# main.net
KiCad netlist of a schematic drawn in Altium Designer
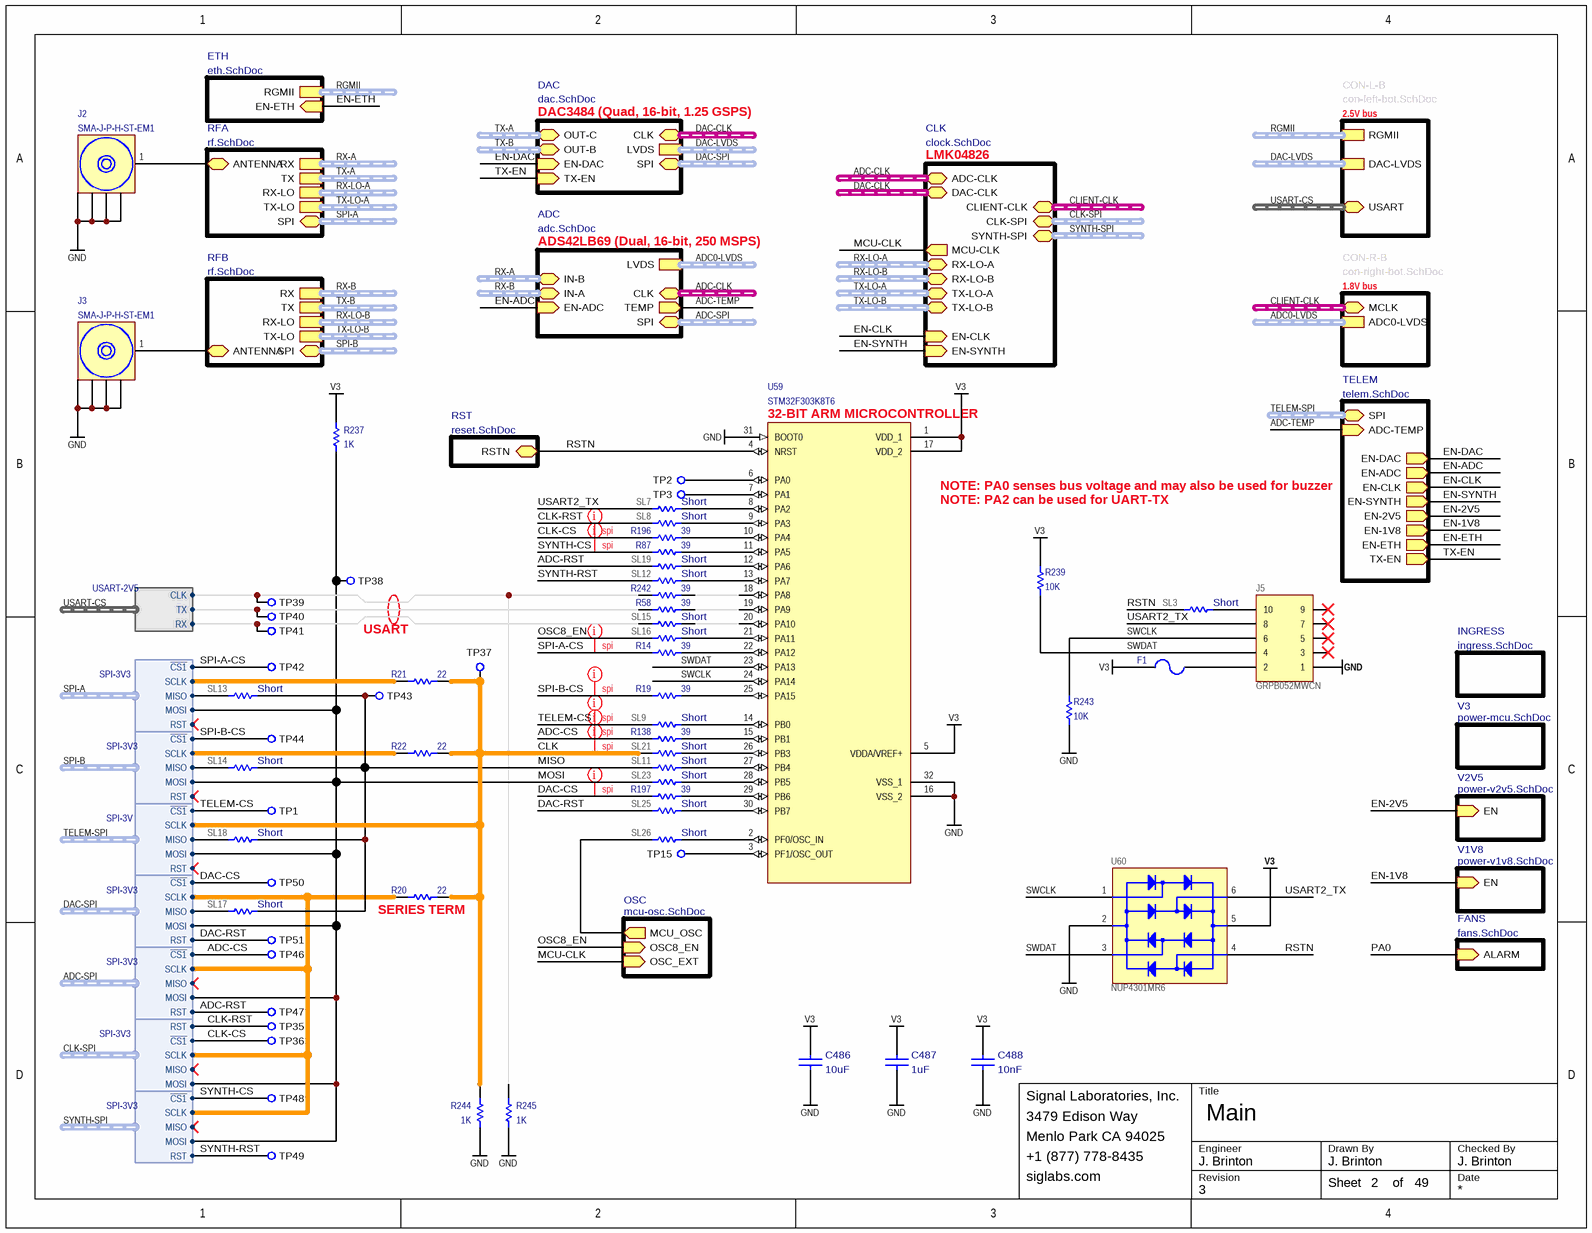
[diagram p0: main.SchDoc]

(export (version "E")
  (design (tool "Eeschema 10.0.6"))
  (components
    (comp (ref "C486")
      (value "10uF")
      (footprint "CAPC200X125X145L45N")
      (description "Ceramic Capacitor 10uF ±10% 16V X7R 0805")
      (fields (field (name "MANUFACTURER") "Samsung") (field (name "TOLERANCE") "±10%"))
      (libsource (lib "capacitors") (part "CAP"))
    )
    (comp (ref "C487")
      (value "1uF")
      (footprint "CAPC200X125X145L45N")
      (description "Ceramic Capacitor 1uF ±10% 25V X7R 0805")
      (fields (field (name "MANUFACTURER") "Taiyo Yuden") (field (name "TOLERANCE") "±10%"))
      (libsource (lib "capacitors") (part "CAP"))
    )
    (comp (ref "C488")
      (value "10nF")
      (footprint "CAPC100X50X55L25N")
      (description "Ceramic Capacitor 10nF ±10% 50V X7R 0402")
      (fields (field (name "MANUFACTURER") "Murata") (field (name "TOLERANCE") "±10%"))
      (libsource (lib "capacitors") (part "CAP"))
    )
    (comp (ref "F1")
      (value "0ZCJ0020FF2E")
      (footprint "generic:1206")
      (description "PTC Resettable Fuse, 0.2A, 30V, SMD 1206")
      (fields (field (name "MANUFACTURER") "Bell Fuse"))
      (libsource (lib "bel-fuse") (part "0ZCJ0020FF2E"))
    )
    (comp (ref "J2")
      (value "SMA-J-P-H-ST-EM1")
      (footprint "samtec:SMA-J-P-H-ST-EM1")
      (description "Edge Mount SMA Jack, Female Socket")
      (fields (field (name "MANUFACTURER") "Samtec"))
      (libsource (lib "amphenol") (part "132136"))
    )
    (comp (ref "J3")
      (value "SMA-J-P-H-ST-EM1")
      (footprint "samtec:SMA-J-P-H-ST-EM1")
      (description "Edge Mount SMA Jack, Female Socket")
      (fields (field (name "MANUFACTURER") "Samtec"))
      (libsource (lib "amphenol") (part "132136"))
    )
    (comp (ref "J5")
      (value "GRPB052MWCN")
      (footprint "sullins:GRPB052MWCN")
      (description "Male Header, 0.050\" Pitch, 2x5 Position, Right Angle")
      (fields (field (name "MANUFACTURER") "Sullins"))
      (libsource (lib "sullins") (part "GRPB052VWVN"))
    )
    (comp (ref "R14")
      (value "39")
      (footprint "RESC1005X40N")
      (description "Thick Film Resistor 39 ±1% 0402")
      (fields (field (name "MANUFACTURER") "Yageo") (field (name "TOLERANCE") "±1%"))
      (libsource (lib "Graviton") (part "RES 0402"))
    )
    (comp (ref "R19")
      (value "39")
      (footprint "RESC1005X40N")
      (description "Thick Film Resistor 39 ±1% 0402")
      (fields (field (name "MANUFACTURER") "Yageo") (field (name "TOLERANCE") "±1%"))
      (libsource (lib "Graviton") (part "RES 0402"))
    )
    (comp (ref "R20")
      (value "22")
      (footprint "RESC1005X40N")
      (description "Thick Film Resistor 22 ±1% 0402")
      (fields (field (name "MANUFACTURER") "Yageo") (field (name "TOLERANCE") "±1%"))
      (libsource (lib "Graviton") (part "RES 0402"))
    )
    (comp (ref "R21")
      (value "22")
      (footprint "RESC1005X40N")
      (description "Thick Film Resistor 22 ±1% 0402")
      (fields (field (name "MANUFACTURER") "Yageo") (field (name "TOLERANCE") "±1%"))
      (libsource (lib "Graviton") (part "RES 0402"))
    )
    (comp (ref "R22")
      (value "22")
      (footprint "RESC1005X40N")
      (description "Thick Film Resistor 22 ±1% 0402")
      (fields (field (name "MANUFACTURER") "Yageo") (field (name "TOLERANCE") "±1%"))
      (libsource (lib "Graviton") (part "RES 0402"))
    )
    (comp (ref "R58")
      (value "39")
      (footprint "RESC1005X40N")
      (description "Thick Film Resistor 39 ±1% 0402")
      (fields (field (name "MANUFACTURER") "Yageo") (field (name "TOLERANCE") "±1%"))
      (libsource (lib "Graviton") (part "RES 0402"))
    )
    (comp (ref "R87")
      (value "39")
      (footprint "RESC1005X40N")
      (description "Thick Film Resistor 39 ±1% 0402")
      (fields (field (name "MANUFACTURER") "Yageo") (field (name "TOLERANCE") "±1%"))
      (libsource (lib "Graviton") (part "RES 0402"))
    )
    (comp (ref "R138")
      (value "39")
      (footprint "RESC1005X40N")
      (description "Thick Film Resistor 39 ±1% 0402")
      (fields (field (name "MANUFACTURER") "Yageo") (field (name "TOLERANCE") "±1%"))
      (libsource (lib "Graviton") (part "RES 0402"))
    )
    (comp (ref "R196")
      (value "39")
      (footprint "RESC1005X40N")
      (description "Thick Film Resistor 39 ±1% 0402")
      (fields (field (name "MANUFACTURER") "Yageo") (field (name "TOLERANCE") "±1%"))
      (libsource (lib "Graviton") (part "RES 0402"))
    )
    (comp (ref "R197")
      (value "39")
      (footprint "RESC1005X40N")
      (description "Thick Film Resistor 39 ±1% 0402")
      (fields (field (name "MANUFACTURER") "Yageo") (field (name "TOLERANCE") "±1%"))
      (libsource (lib "Graviton") (part "RES 0402"))
    )
    (comp (ref "R237")
      (value "1K")
      (footprint "RESC1005X40N")
      (description "Thick Film Resistor 1k ±1% 0402")
      (fields (field (name "MANUFACTURER") "Yageo") (field (name "TOLERANCE") "±1%"))
      (libsource (lib "Graviton") (part "RES 0402"))
    )
    (comp (ref "R239")
      (value "10K")
      (footprint "RESC1005X40N")
      (description "Thick Film Resistor 10k ±1% 0.1W 50V 0402")
      (fields (field (name "MANUFACTURER") "Panasonic") (field (name "TOLERANCE") "±1%"))
      (libsource (lib "Graviton") (part "RES 0402"))
    )
    (comp (ref "R242")
      (value "39")
      (footprint "RESC1005X40N")
      (description "Thick Film Resistor 39 ±1% 0402")
      (fields (field (name "MANUFACTURER") "Yageo") (field (name "TOLERANCE") "±1%"))
      (libsource (lib "Graviton") (part "RES 0402"))
    )
    (comp (ref "R243")
      (value "10K")
      (footprint "RESC1005X40N")
      (description "Thick Film Resistor 10k ±1% 0.1W 50V 0402")
      (fields (field (name "MANUFACTURER") "Panasonic") (field (name "TOLERANCE") "±1%"))
      (libsource (lib "Graviton") (part "RES 0402"))
    )
    (comp (ref "R244")
      (value "1K")
      (footprint "RESC1005X40N")
      (description "Thick Film Resistor 1k ±1% 0402")
      (fields (field (name "MANUFACTURER") "Yageo") (field (name "TOLERANCE") "±1%"))
      (libsource (lib "Graviton") (part "RES 0402"))
    )
    (comp (ref "R245")
      (value "1K")
      (footprint "RESC1005X40N")
      (description "Thick Film Resistor 1k ±1% 0402")
      (fields (field (name "MANUFACTURER") "Yageo") (field (name "TOLERANCE") "±1%"))
      (libsource (lib "Graviton") (part "RES 0402"))
    )
    (comp (ref "SL3")
      (value "SOLDER_LINK")
      (footprint "SOLDERLINK0603X26N_BRIDGED")
      (description "Solder Link, Bridged")
      (fields (field (name "NOTES") "Short"))
      (libsource (lib "generic") (part "RES"))
    )
    (comp (ref "SL7")
      (value "SOLDER_LINK")
      (footprint "SOLDERLINK0603X26N_BRIDGED")
      (description "Solder Link, Bridged")
      (fields (field (name "NOTES") "Short"))
      (libsource (lib "generic") (part "RES"))
    )
    (comp (ref "SL8")
      (value "SOLDER_LINK")
      (footprint "SOLDERLINK0603X26N_BRIDGED")
      (description "Solder Link, Bridged")
      (fields (field (name "NOTES") "Short"))
      (libsource (lib "generic") (part "RES"))
    )
    (comp (ref "SL9")
      (value "SOLDER_LINK")
      (footprint "SOLDERLINK0603X26N_BRIDGED")
      (description "Solder Link, Bridged")
      (fields (field (name "NOTES") "Short"))
      (libsource (lib "generic") (part "RES"))
    )
    (comp (ref "SL11")
      (value "SOLDER_LINK")
      (footprint "SOLDERLINK0603X26N_BRIDGED")
      (description "Solder Link, Bridged")
      (fields (field (name "NOTES") "Short"))
      (libsource (lib "generic") (part "RES"))
    )
    (comp (ref "SL12")
      (value "SOLDER_LINK")
      (footprint "SOLDERLINK0603X26N_BRIDGED")
      (description "Solder Link, Bridged")
      (fields (field (name "NOTES") "Short"))
      (libsource (lib "generic") (part "RES"))
    )
    (comp (ref "SL13")
      (value "SOLDER_LINK")
      (footprint "SOLDERLINK0603X26N_BRIDGED")
      (description "Solder Link, Bridged")
      (fields (field (name "NOTES") "Short"))
      (libsource (lib "generic") (part "RES"))
    )
    (comp (ref "SL14")
      (value "SOLDER_LINK")
      (footprint "SOLDERLINK0603X26N_BRIDGED")
      (description "Solder Link, Bridged")
      (fields (field (name "NOTES") "Short"))
      (libsource (lib "generic") (part "RES"))
    )
    (comp (ref "SL15")
      (value "SOLDER_LINK")
      (footprint "SOLDERLINK0603X26N_BRIDGED")
      (description "Solder Link, Bridged")
      (fields (field (name "NOTES") "Short"))
      (libsource (lib "generic") (part "RES"))
    )
    (comp (ref "SL16")
      (value "SOLDER_LINK")
      (footprint "SOLDERLINK0603X26N_BRIDGED")
      (description "Solder Link, Bridged")
      (fields (field (name "NOTES") "Short"))
      (libsource (lib "generic") (part "RES"))
    )
    (comp (ref "SL17")
      (value "SOLDER_LINK")
      (footprint "SOLDERLINK0603X26N_BRIDGED")
      (description "Solder Link, Bridged")
      (fields (field (name "NOTES") "Short"))
      (libsource (lib "generic") (part "RES"))
    )
    (comp (ref "SL18")
      (value "SOLDER_LINK")
      (footprint "SOLDERLINK0603X26N_BRIDGED")
      (description "Solder Link, Bridged")
      (fields (field (name "NOTES") "Short"))
      (libsource (lib "generic") (part "RES"))
    )
    (comp (ref "SL19")
      (value "SOLDER_LINK")
      (footprint "SOLDERLINK0603X26N_BRIDGED")
      (description "Solder Link, Bridged")
      (fields (field (name "NOTES") "Short"))
      (libsource (lib "generic") (part "RES"))
    )
    (comp (ref "SL21")
      (value "SOLDER_LINK")
      (footprint "SOLDERLINK0603X26N_BRIDGED")
      (description "Solder Link, Bridged")
      (fields (field (name "NOTES") "Short"))
      (libsource (lib "generic") (part "RES"))
    )
    (comp (ref "SL23")
      (value "SOLDER_LINK")
      (footprint "SOLDERLINK0603X26N_BRIDGED")
      (description "Solder Link, Bridged")
      (fields (field (name "NOTES") "Short"))
      (libsource (lib "generic") (part "RES"))
    )
    (comp (ref "SL25")
      (value "SOLDER_LINK")
      (footprint "SOLDERLINK0603X26N_BRIDGED")
      (description "Solder Link, Bridged")
      (fields (field (name "NOTES") "Short"))
      (libsource (lib "generic") (part "RES"))
    )
    (comp (ref "SL26")
      (value "SOLDER_LINK")
      (footprint "SOLDERLINK0603X26N_BRIDGED")
      (description "Solder Link, Bridged")
      (fields (field (name "NOTES") "Short"))
      (libsource (lib "generic") (part "RES"))
    )
    (comp (ref "TP1")
      (value "TEST_POINT_SMD_50")
      (footprint "generic:TEST_POINT_SMD_10")
      (description "Test Point SMD")
      (libsource (lib "generic") (part "TEST_POINT_SMD_50"))
    )
    (comp (ref "TP2")
      (value "TEST_POINT_SMD_10")
      (footprint "generic:TEST_POINT_SMD_10")
      (description "Test Point SMD")
      (libsource (lib "generic") (part "TEST_POINT_SMD_10"))
    )
    (comp (ref "TP3")
      (value "TEST_POINT_SMD_10")
      (footprint "generic:TEST_POINT_SMD_10")
      (description "Test Point SMD")
      (libsource (lib "generic") (part "TEST_POINT_SMD_10"))
    )
    (comp (ref "TP15")
      (value "TEST_POINT_SMD_10")
      (footprint "generic:TEST_POINT_SMD_10")
      (description "Test Point SMD")
      (libsource (lib "generic") (part "TEST_POINT_SMD_10"))
    )
    (comp (ref "TP35")
      (value "TEST_POINT_SMD_50")
      (footprint "generic:TEST_POINT_SMD_10")
      (description "Test Point SMD")
      (libsource (lib "generic") (part "TEST_POINT_SMD_50"))
    )
    (comp (ref "TP36")
      (value "TEST_POINT_SMD_50")
      (footprint "generic:TEST_POINT_SMD_10")
      (description "Test Point SMD")
      (libsource (lib "generic") (part "TEST_POINT_SMD_50"))
    )
    (comp (ref "TP37")
      (value "TEST_POINT_SMD_50")
      (footprint "generic:TEST_POINT_SMD_10")
      (description "Test Point SMD")
      (libsource (lib "generic") (part "TEST_POINT_SMD_50"))
    )
    (comp (ref "TP38")
      (value "TEST_POINT_SMD_50")
      (footprint "generic:TEST_POINT_SMD_10")
      (description "Test Point SMD")
      (libsource (lib "generic") (part "TEST_POINT_SMD_50"))
    )
    (comp (ref "TP39")
      (value "TEST_POINT_SMD_50")
      (footprint "generic:TEST_POINT_SMD_10")
      (description "Test Point SMD")
      (libsource (lib "generic") (part "TEST_POINT_SMD_50"))
    )
    (comp (ref "TP40")
      (value "TEST_POINT_SMD_50")
      (footprint "generic:TEST_POINT_SMD_10")
      (description "Test Point SMD")
      (libsource (lib "generic") (part "TEST_POINT_SMD_50"))
    )
    (comp (ref "TP41")
      (value "TEST_POINT_SMD_50")
      (footprint "generic:TEST_POINT_SMD_10")
      (description "Test Point SMD")
      (libsource (lib "generic") (part "TEST_POINT_SMD_50"))
    )
    (comp (ref "TP42")
      (value "TEST_POINT_SMD_50")
      (footprint "generic:TEST_POINT_SMD_10")
      (description "Test Point SMD")
      (libsource (lib "generic") (part "TEST_POINT_SMD_50"))
    )
    (comp (ref "TP43")
      (value "TEST_POINT_SMD_50")
      (footprint "generic:TEST_POINT_SMD_10")
      (description "Test Point SMD")
      (libsource (lib "generic") (part "TEST_POINT_SMD_50"))
    )
    (comp (ref "TP44")
      (value "TEST_POINT_SMD_50")
      (footprint "generic:TEST_POINT_SMD_10")
      (description "Test Point SMD")
      (libsource (lib "generic") (part "TEST_POINT_SMD_50"))
    )
    (comp (ref "TP46")
      (value "TEST_POINT_SMD_50")
      (footprint "generic:TEST_POINT_SMD_10")
      (description "Test Point SMD")
      (libsource (lib "generic") (part "TEST_POINT_SMD_50"))
    )
    (comp (ref "TP47")
      (value "TEST_POINT_SMD_50")
      (footprint "generic:TEST_POINT_SMD_10")
      (description "Test Point SMD")
      (libsource (lib "generic") (part "TEST_POINT_SMD_50"))
    )
    (comp (ref "TP48")
      (value "TEST_POINT_SMD_50")
      (footprint "generic:TEST_POINT_SMD_10")
      (description "Test Point SMD")
      (libsource (lib "generic") (part "TEST_POINT_SMD_50"))
    )
    (comp (ref "TP49")
      (value "TEST_POINT_SMD_50")
      (footprint "generic:TEST_POINT_SMD_10")
      (description "Test Point SMD")
      (libsource (lib "generic") (part "TEST_POINT_SMD_50"))
    )
    (comp (ref "TP50")
      (value "TEST_POINT_SMD_50")
      (footprint "generic:TEST_POINT_SMD_10")
      (description "Test Point SMD")
      (libsource (lib "generic") (part "TEST_POINT_SMD_50"))
    )
    (comp (ref "TP51")
      (value "TEST_POINT_SMD_50")
      (footprint "generic:TEST_POINT_SMD_10")
      (description "Test Point SMD")
      (libsource (lib "generic") (part "TEST_POINT_SMD_50"))
    )
    (comp (ref "U59")
      (value "STM32F303K8T6")
      (footprint "st:QFP80P900X900X160-32N")
      (description "ARM Cortex-M4 MCU + FPU")
      (fields (field (name "MANUFACTURER") "STMicroelectronics"))
      (libsource (lib "st") (part "STM32F303K8T6"))
    )
    (comp (ref "U60")
      (value "NUP4301MR6")
      (footprint "generic:SOT23-6")
      (description "4-Lane TVS Diode Array")
      (fields (field (name "MANUFACTURER") "On Semiconductor"))
      (libsource (lib "on_semi") (part "NUP4301MR6"))
    )
  )
  (nets
    (net (code "29") (name "/ADC-CS") (class "Default")
      (node (ref "R138") (pin "1") (pinfunction "1_1") (pintype "passive"))
      (node (ref "TP46") (pin "1") (pinfunction "1_1") (pintype "passive"))
    )
    (net (code "30") (name "/ADC-RST") (class "Default")
      (node (ref "SL19") (pin "2") (pinfunction "2_2") (pintype "passive"))
      (node (ref "TP47") (pin "1") (pinfunction "1_1") (pintype "passive"))
    )
    (net (code "33") (name "/ANTENNA") (class "Default")
      (node (ref "J2") (pin "1") (pinfunction "CENTER_1") (pintype "passive"))
    )
    (net (code "34") (name "/ANTENNA_1") (class "Default")
      (node (ref "J3") (pin "1") (pinfunction "CENTER_1") (pintype "passive"))
    )
    (net (code "35") (name "/CLK") (class "Default")
      (node (ref "R20") (pin "2") (pinfunction "2_2") (pintype "passive"))
      (node (ref "R21") (pin "2") (pinfunction "2_2") (pintype "passive"))
      (node (ref "R22") (pin "2") (pinfunction "2_2") (pintype "passive"))
      (node (ref "R244") (pin "2") (pinfunction "2_2") (pintype "passive"))
      (node (ref "SL21") (pin "2") (pinfunction "2_2") (pintype "passive"))
      (node (ref "TP37") (pin "1") (pinfunction "1_1") (pintype "passive"))
    )
    (net (code "36") (name "/CLK-CS") (class "Default")
      (node (ref "R196") (pin "1") (pinfunction "1_1") (pintype "passive"))
      (node (ref "TP36") (pin "1") (pinfunction "1_1") (pintype "passive"))
    )
    (net (code "37") (name "/CLK-RST") (class "Default")
      (node (ref "SL8") (pin "2") (pinfunction "2_2") (pintype "passive"))
      (node (ref "TP35") (pin "1") (pinfunction "1_1") (pintype "passive"))
    )
    (net (code "39") (name "/DAC-CS") (class "Default")
      (node (ref "R197") (pin "1") (pinfunction "1_1") (pintype "passive"))
      (node (ref "TP50") (pin "1") (pinfunction "1_1") (pintype "passive"))
    )
    (net (code "40") (name "/DAC-RST") (class "Default")
      (node (ref "SL25") (pin "2") (pinfunction "2_2") (pintype "passive"))
      (node (ref "TP51") (pin "1") (pinfunction "1_1") (pintype "passive"))
    )
    (net (code "49") (name "/MCU_OSC") (class "Default")
      (node (ref "SL26") (pin "2") (pinfunction "2_2") (pintype "passive"))
    )
    (net (code "50") (name "/MISO") (class "Default")
      (node (ref "SL11") (pin "2") (pinfunction "2_2") (pintype "passive"))
      (node (ref "SL13") (pin "1") (pinfunction "1_1") (pintype "passive"))
      (node (ref "SL14") (pin "1") (pinfunction "1_1") (pintype "passive"))
      (node (ref "SL17") (pin "1") (pinfunction "1_1") (pintype "passive"))
      (node (ref "SL18") (pin "1") (pinfunction "1_1") (pintype "passive"))
      (node (ref "TP43") (pin "1") (pinfunction "1_1") (pintype "passive"))
    )
    (net (code "51") (name "/MOSI") (class "Default")
      (node (ref "R237") (pin "1") (pinfunction "1_1") (pintype "passive"))
      (node (ref "SL23") (pin "2") (pinfunction "2_2") (pintype "passive"))
      (node (ref "TP38") (pin "1") (pinfunction "1_1") (pintype "passive"))
    )
    (net (code "52") (name "/OSC8_EN") (class "Default")
      (node (ref "SL16") (pin "2") (pinfunction "2_2") (pintype "passive"))
    )
    (net (code "54") (name "/RSTN") (class "Default")
      (node (ref "SL3") (pin "2") (pinfunction "2_2") (pintype "passive"))
      (node (ref "U59") (pin "4") (pinfunction "NRST_4") (pintype "bidirectional"))
      (node (ref "U60") (pin "4") (pinfunction "C_4") (pintype "passive"))
    )
    (net (code "55") (name "/RX") (class "Default")
      (node (ref "SL15") (pin "2") (pinfunction "2_2") (pintype "passive"))
      (node (ref "TP41") (pin "1") (pinfunction "1_1") (pintype "passive"))
    )
    (net (code "56") (name "/SPI-A-CS") (class "Default")
      (node (ref "R14") (pin "1") (pinfunction "1_1") (pintype "passive"))
      (node (ref "TP42") (pin "1") (pinfunction "1_1") (pintype "passive"))
    )
    (net (code "57") (name "/SPI-B-CS") (class "Default")
      (node (ref "R19") (pin "1") (pinfunction "1_1") (pintype "passive"))
      (node (ref "TP44") (pin "1") (pinfunction "1_1") (pintype "passive"))
    )
    (net (code "58") (name "/SWCLK") (class "Default")
      (node (ref "J5") (pin "6") (pinfunction "6_6") (pintype "passive"))
      (node (ref "R243") (pin "2") (pinfunction "2_2") (pintype "passive"))
      (node (ref "U59") (pin "24") (pinfunction "PA14_24") (pintype "bidirectional"))
      (node (ref "U60") (pin "1") (pinfunction "A_1") (pintype "passive"))
    )
    (net (code "59") (name "/SWDAT") (class "Default")
      (node (ref "J5") (pin "4") (pinfunction "4_4") (pintype "passive"))
      (node (ref "R239") (pin "1") (pinfunction "1_1") (pintype "passive"))
      (node (ref "U59") (pin "23") (pinfunction "PA13_23") (pintype "bidirectional"))
      (node (ref "U60") (pin "3") (pinfunction "B_3") (pintype "passive"))
    )
    (net (code "60") (name "/SYNTH-CS") (class "Default")
      (node (ref "R87") (pin "1") (pinfunction "1_1") (pintype "passive"))
      (node (ref "TP48") (pin "1") (pinfunction "1_1") (pintype "passive"))
    )
    (net (code "61") (name "/SYNTH-RST") (class "Default")
      (node (ref "SL12") (pin "2") (pinfunction "2_2") (pintype "passive"))
      (node (ref "TP49") (pin "1") (pinfunction "1_1") (pintype "passive"))
    )
    (net (code "63") (name "/TELEM-CS") (class "Default")
      (node (ref "SL9") (pin "2") (pinfunction "2_2") (pintype "passive"))
      (node (ref "TP1") (pin "1") (pinfunction "1_1") (pintype "passive"))
    )
    (net (code "65") (name "/TX") (class "Default")
      (node (ref "R58") (pin "1") (pinfunction "1_1") (pintype "passive"))
      (node (ref "TP40") (pin "1") (pinfunction "1_1") (pintype "passive"))
    )
    (net (code "68") (name "/USART2_TX") (class "Default")
      (node (ref "J5") (pin "8") (pinfunction "8_8") (pintype "passive"))
      (node (ref "SL7") (pin "2") (pinfunction "2_2") (pintype "passive"))
      (node (ref "U60") (pin "6") (pinfunction "D_6") (pintype "passive"))
    )
    (net (code "91") (name "GND") (class "Default")
      (node (ref "C486") (pin "2") (pinfunction "2_2") (pintype "passive"))
      (node (ref "C487") (pin "2") (pinfunction "2_2") (pintype "passive"))
      (node (ref "C488") (pin "2") (pinfunction "2_2") (pintype "passive"))
      (node (ref "J2") (pin "2") (pinfunction "GND_2") (pintype "passive"))
      (node (ref "J2") (pin "3") (pinfunction "GND_3") (pintype "passive"))
      (node (ref "J2") (pin "4") (pinfunction "GND_4") (pintype "passive"))
      (node (ref "J2") (pin "5") (pinfunction "GND_5") (pintype "passive"))
      (node (ref "J3") (pin "2") (pinfunction "GND_2") (pintype "passive"))
      (node (ref "J3") (pin "3") (pinfunction "GND_3") (pintype "passive"))
      (node (ref "J3") (pin "4") (pinfunction "GND_4") (pintype "passive"))
      (node (ref "J3") (pin "5") (pinfunction "GND_5") (pintype "passive"))
      (node (ref "J5") (pin "1") (pinfunction "1_1") (pintype "passive"))
      (node (ref "R243") (pin "1") (pinfunction "1_1") (pintype "passive"))
      (node (ref "R244") (pin "1") (pinfunction "1_1") (pintype "passive"))
      (node (ref "R245") (pin "1") (pinfunction "1_1") (pintype "passive"))
      (node (ref "U59") (pin "16") (pinfunction "VSS_2_16") (pintype "power_in"))
      (node (ref "U59") (pin "31") (pinfunction "BOOT0_31") (pintype "input"))
      (node (ref "U59") (pin "32") (pinfunction "VSS_1_32") (pintype "power_in"))
      (node (ref "U60") (pin "2") (pinfunction "VN_2") (pintype "passive"))
    )
    (net (code "92") (name "Net-(F1-Pad1)") (class "Default")
      (node (ref "F1") (pin "1") (pinfunction "1_1") (pintype "passive"))
      (node (ref "J5") (pin "2") (pinfunction "2_2") (pintype "passive"))
    )
    (net (code "93") (name "Net-(J5-Pad10)") (class "Default")
      (node (ref "J5") (pin "10") (pinfunction "10_10") (pintype "passive"))
      (node (ref "SL3") (pin "1") (pinfunction "1_1") (pintype "passive"))
    )
    (net (code "94") (name "Net-(R242-Pad1)") (class "Default")
      (node (ref "R242") (pin "1") (pinfunction "1_1") (pintype "passive"))
      (node (ref "R245") (pin "2") (pinfunction "2_2") (pintype "passive"))
      (node (ref "TP39") (pin "1") (pinfunction "1_1") (pintype "passive"))
    )
    (net (code "95") (name "Net-(U59-PA0)") (class "Default")
      (node (ref "TP2") (pin "1") (pinfunction "1_1") (pintype "passive"))
      (node (ref "U59") (pin "6") (pinfunction "PA0_6") (pintype "bidirectional"))
    )
    (net (code "96") (name "Net-(U59-PA1)") (class "Default")
      (node (ref "TP3") (pin "1") (pinfunction "1_1") (pintype "passive"))
      (node (ref "U59") (pin "7") (pinfunction "PA1_7") (pintype "bidirectional"))
    )
    (net (code "97") (name "Net-(U59-PA2)") (class "Default")
      (node (ref "SL7") (pin "1") (pinfunction "1_1") (pintype "passive"))
      (node (ref "U59") (pin "8") (pinfunction "PA2_8") (pintype "bidirectional"))
    )
    (net (code "98") (name "Net-(U59-PA3)") (class "Default")
      (node (ref "SL8") (pin "1") (pinfunction "1_1") (pintype "passive"))
      (node (ref "U59") (pin "9") (pinfunction "PA3_9") (pintype "bidirectional"))
    )
    (net (code "99") (name "Net-(U59-PA4)") (class "Default")
      (node (ref "R196") (pin "2") (pinfunction "2_2") (pintype "passive"))
      (node (ref "U59") (pin "10") (pinfunction "PA4_10") (pintype "bidirectional"))
    )
    (net (code "100") (name "Net-(U59-PA5)") (class "Default")
      (node (ref "R87") (pin "2") (pinfunction "2_2") (pintype "passive"))
      (node (ref "U59") (pin "11") (pinfunction "PA5_11") (pintype "bidirectional"))
    )
    (net (code "101") (name "Net-(U59-PA6)") (class "Default")
      (node (ref "SL19") (pin "1") (pinfunction "1_1") (pintype "passive"))
      (node (ref "U59") (pin "12") (pinfunction "PA6_12") (pintype "bidirectional"))
    )
    (net (code "102") (name "Net-(U59-PA7)") (class "Default")
      (node (ref "SL12") (pin "1") (pinfunction "1_1") (pintype "passive"))
      (node (ref "U59") (pin "13") (pinfunction "PA7_13") (pintype "bidirectional"))
    )
    (net (code "103") (name "Net-(U59-PA8)") (class "Default")
      (node (ref "R242") (pin "2") (pinfunction "2_2") (pintype "passive"))
      (node (ref "U59") (pin "18") (pinfunction "PA8_18") (pintype "bidirectional"))
    )
    (net (code "104") (name "Net-(U59-PA9)") (class "Default")
      (node (ref "R58") (pin "2") (pinfunction "2_2") (pintype "passive"))
      (node (ref "U59") (pin "19") (pinfunction "PA9_19") (pintype "bidirectional"))
    )
    (net (code "105") (name "Net-(U59-PA10)") (class "Default")
      (node (ref "SL15") (pin "1") (pinfunction "1_1") (pintype "passive"))
      (node (ref "U59") (pin "20") (pinfunction "PA10_20") (pintype "bidirectional"))
    )
    (net (code "106") (name "Net-(U59-PA11)") (class "Default")
      (node (ref "SL16") (pin "1") (pinfunction "1_1") (pintype "passive"))
      (node (ref "U59") (pin "21") (pinfunction "PA11_21") (pintype "bidirectional"))
    )
    (net (code "107") (name "Net-(U59-PA12)") (class "Default")
      (node (ref "R14") (pin "2") (pinfunction "2_2") (pintype "passive"))
      (node (ref "U59") (pin "22") (pinfunction "PA12_22") (pintype "bidirectional"))
    )
    (net (code "108") (name "Net-(U59-PA15)") (class "Default")
      (node (ref "R19") (pin "2") (pinfunction "2_2") (pintype "passive"))
      (node (ref "U59") (pin "25") (pinfunction "PA15_25") (pintype "bidirectional"))
    )
    (net (code "109") (name "Net-(U59-PB0)") (class "Default")
      (node (ref "SL9") (pin "1") (pinfunction "1_1") (pintype "passive"))
      (node (ref "U59") (pin "14") (pinfunction "PB0_14") (pintype "bidirectional"))
    )
    (net (code "110") (name "Net-(U59-PB1)") (class "Default")
      (node (ref "R138") (pin "2") (pinfunction "2_2") (pintype "passive"))
      (node (ref "U59") (pin "15") (pinfunction "PB1_15") (pintype "bidirectional"))
    )
    (net (code "111") (name "Net-(U59-PB3)") (class "Default")
      (node (ref "SL21") (pin "1") (pinfunction "1_1") (pintype "passive"))
      (node (ref "U59") (pin "26") (pinfunction "PB3_26") (pintype "bidirectional"))
    )
    (net (code "112") (name "Net-(U59-PB4)") (class "Default")
      (node (ref "SL11") (pin "1") (pinfunction "1_1") (pintype "passive"))
      (node (ref "U59") (pin "27") (pinfunction "PB4_27") (pintype "bidirectional"))
    )
    (net (code "113") (name "Net-(U59-PB5)") (class "Default")
      (node (ref "SL23") (pin "1") (pinfunction "1_1") (pintype "passive"))
      (node (ref "U59") (pin "28") (pinfunction "PB5_28") (pintype "bidirectional"))
    )
    (net (code "114") (name "Net-(U59-PB6)") (class "Default")
      (node (ref "R197") (pin "2") (pinfunction "2_2") (pintype "passive"))
      (node (ref "U59") (pin "29") (pinfunction "PB6_29") (pintype "bidirectional"))
    )
    (net (code "115") (name "Net-(U59-PB7)") (class "Default")
      (node (ref "SL25") (pin "1") (pinfunction "1_1") (pintype "passive"))
      (node (ref "U59") (pin "30") (pinfunction "PB7_30") (pintype "bidirectional"))
    )
    (net (code "116") (name "Net-(U59-PF0{slash}OSC_IN)") (class "Default")
      (node (ref "SL26") (pin "1") (pinfunction "1_1") (pintype "passive"))
      (node (ref "U59") (pin "2") (pinfunction "PF0/OSC_IN_2") (pintype "bidirectional"))
    )
    (net (code "117") (name "Net-(U59-PF1{slash}OSC_OUT)") (class "Default")
      (node (ref "TP15") (pin "1") (pinfunction "1_1") (pintype "passive"))
      (node (ref "U59") (pin "3") (pinfunction "PF1/OSC_OUT_3") (pintype "bidirectional"))
    )
    (net (code "118") (name "V3") (class "Default")
      (node (ref "C486") (pin "1") (pinfunction "1_1") (pintype "passive"))
      (node (ref "C487") (pin "1") (pinfunction "1_1") (pintype "passive"))
      (node (ref "C488") (pin "1") (pinfunction "1_1") (pintype "passive"))
      (node (ref "F1") (pin "2") (pinfunction "2_2") (pintype "passive"))
      (node (ref "R237") (pin "2") (pinfunction "2_2") (pintype "passive"))
      (node (ref "R239") (pin "2") (pinfunction "2_2") (pintype "passive"))
      (node (ref "U59") (pin "1") (pinfunction "VDD_1_1") (pintype "power_in"))
      (node (ref "U59") (pin "17") (pinfunction "VDD_2_17") (pintype "power_in"))
      (node (ref "U59") (pin "5") (pinfunction "VDDA/VREF+_5") (pintype "power_in"))
      (node (ref "U60") (pin "5") (pinfunction "VP_5") (pintype "passive"))
    )
    (net (code "119") (name "unconnected-(J5-Pad3)") (class "Default")
      (node (ref "J5") (pin "3") (pinfunction "3_3") (pintype "passive+no_connect"))
    )
    (net (code "120") (name "unconnected-(J5-Pad5)") (class "Default")
      (node (ref "J5") (pin "5") (pinfunction "5_5") (pintype "passive+no_connect"))
    )
    (net (code "121") (name "unconnected-(J5-Pad7)") (class "Default")
      (node (ref "J5") (pin "7") (pinfunction "7_7") (pintype "passive+no_connect"))
    )
    (net (code "122") (name "unconnected-(J5-Pad9)") (class "Default")
      (node (ref "J5") (pin "9") (pinfunction "9_9") (pintype "passive+no_connect"))
    )
    (net (code "123") (name "unconnected-(R20-Pad1)") (class "Default")
      (node (ref "R20") (pin "1") (pinfunction "1_1") (pintype "passive"))
    )
    (net (code "124") (name "unconnected-(R21-Pad1)") (class "Default")
      (node (ref "R21") (pin "1") (pinfunction "1_1") (pintype "passive"))
    )
    (net (code "125") (name "unconnected-(R22-Pad1)") (class "Default")
      (node (ref "R22") (pin "1") (pinfunction "1_1") (pintype "passive"))
    )
    (net (code "126") (name "unconnected-(SL13-Pad2)") (class "Default")
      (node (ref "SL13") (pin "2") (pinfunction "2_2") (pintype "passive"))
    )
    (net (code "127") (name "unconnected-(SL14-Pad2)") (class "Default")
      (node (ref "SL14") (pin "2") (pinfunction "2_2") (pintype "passive"))
    )
    (net (code "128") (name "unconnected-(SL17-Pad2)") (class "Default")
      (node (ref "SL17") (pin "2") (pinfunction "2_2") (pintype "passive"))
    )
    (net (code "129") (name "unconnected-(SL18-Pad2)") (class "Default")
      (node (ref "SL18") (pin "2") (pinfunction "2_2") (pintype "passive"))
    )
  )
)
